# open-bldc-logic.net
KiCad netlist of a schematic drawn in EAGLE
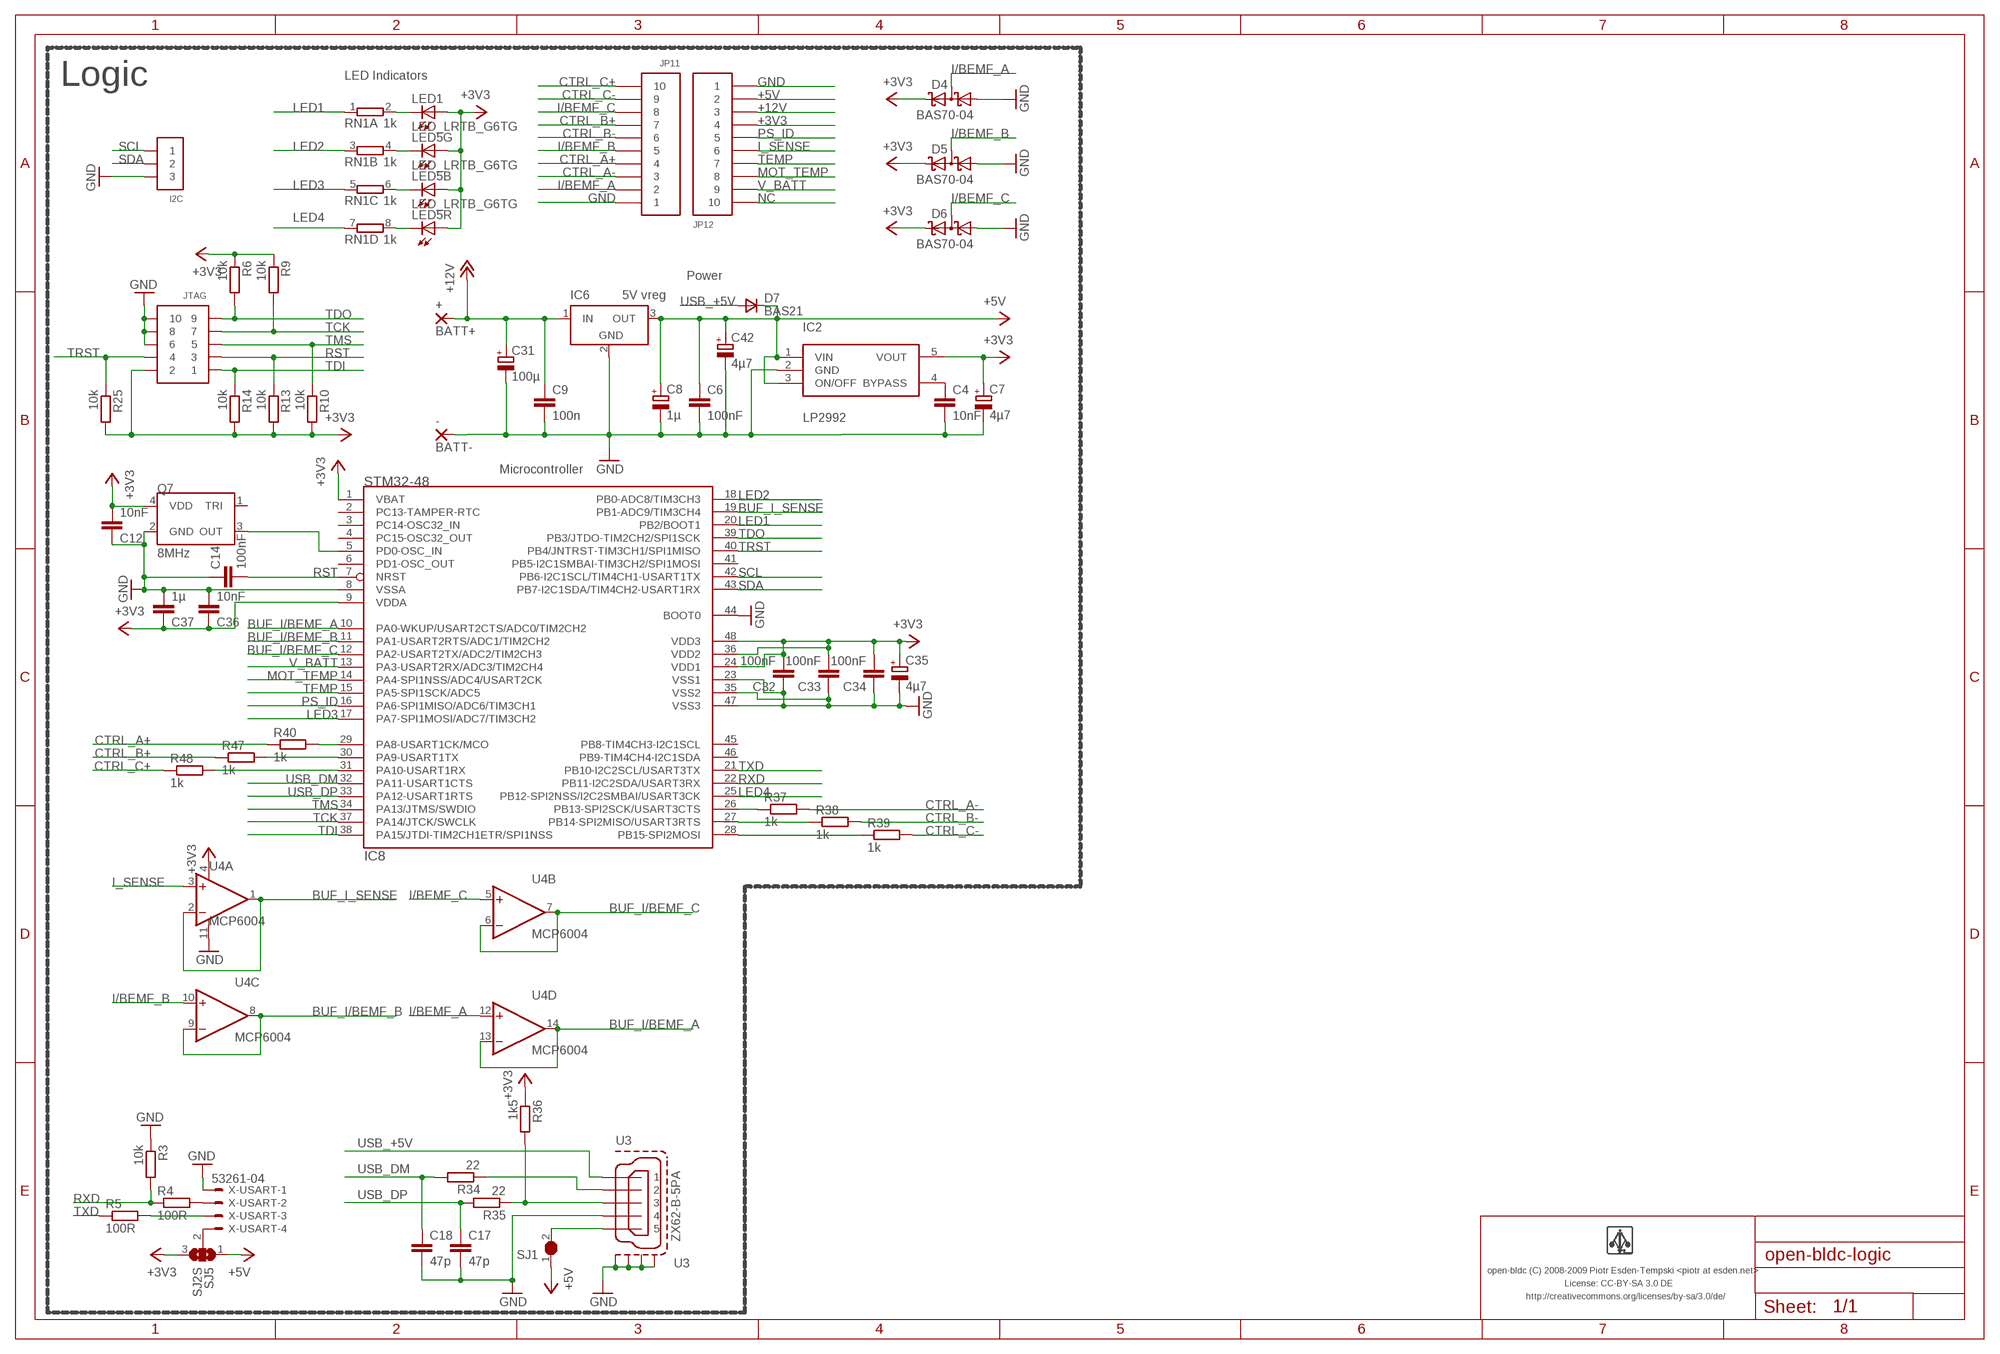
[diagram p0: schematic, sheet 1]

(export (version "E")
  (design (tool "Eeschema 10.0.6"))
  (components
    (comp (ref "+")
      (value "BATT+")
      (footprint "eagle-import:SMD2,54-5,08")
      (libsource (lib "eagle-import") (part "SMD5"))
    )
    (comp (ref "-")
      (value "BATT-")
      (footprint "eagle-import:SMD2,54-5,08")
      (libsource (lib "eagle-import") (part "SMD5"))
    )
    (comp (ref "C4")
      (value "10nF")
      (footprint "eagle-import:C0603")
      (libsource (lib "eagle-import") (part "C-EUC0603"))
    )
    (comp (ref "C6")
      (value "100nF")
      (footprint "eagle-import:C0603")
      (libsource (lib "eagle-import") (part "C-EUC0603"))
    )
    (comp (ref "C7")
      (value "4µ7")
      (footprint "eagle-import:A_3216-18R")
      (libsource (lib "eagle-import") (part "CPOL-EUA/3216-18R"))
    )
    (comp (ref "C8")
      (value "1µ")
      (footprint "eagle-import:A_3216-18R")
      (libsource (lib "eagle-import") (part "CPOL-EUA/3216-18R"))
    )
    (comp (ref "C9")
      (value "100n")
      (footprint "eagle-import:C0603")
      (libsource (lib "eagle-import") (part "C-EUC0603"))
    )
    (comp (ref "C12")
      (value "10nF")
      (footprint "eagle-import:C0603")
      (libsource (lib "eagle-import") (part "C-EUC0603"))
    )
    (comp (ref "C14")
      (value "100nF")
      (footprint "eagle-import:C0603")
      (libsource (lib "eagle-import") (part "C-EUC0603"))
    )
    (comp (ref "C17")
      (value "47p")
      (footprint "eagle-import:C0603")
      (libsource (lib "eagle-import") (part "C-EUC0603"))
    )
    (comp (ref "C18")
      (value "47p")
      (footprint "eagle-import:C0603")
      (libsource (lib "eagle-import") (part "C-EUC0603"))
    )
    (comp (ref "C31")
      (value "100µ")
      (footprint "eagle-import:D_7343-31R")
      (libsource (lib "eagle-import") (part "CPOL-EUD/7343-31R"))
    )
    (comp (ref "C32")
      (value "100nF")
      (footprint "eagle-import:C0603")
      (libsource (lib "eagle-import") (part "C-EUC0603"))
    )
    (comp (ref "C33")
      (value "100nF")
      (footprint "eagle-import:C0603")
      (libsource (lib "eagle-import") (part "C-EUC0603"))
    )
    (comp (ref "C34")
      (value "100nF")
      (footprint "eagle-import:C0603")
      (libsource (lib "eagle-import") (part "C-EUC0603"))
    )
    (comp (ref "C35")
      (value "4µ7")
      (footprint "eagle-import:A_3216-18R")
      (libsource (lib "eagle-import") (part "CPOL-EUA/3216-18R"))
    )
    (comp (ref "C36")
      (value "10nF")
      (footprint "eagle-import:C0603")
      (libsource (lib "eagle-import") (part "C-EUC0603"))
    )
    (comp (ref "C37")
      (value "1µ")
      (footprint "eagle-import:C0603")
      (libsource (lib "eagle-import") (part "C-EUC0603"))
    )
    (comp (ref "C42")
      (value "4µ7")
      (footprint "eagle-import:A_3216-18R")
      (libsource (lib "eagle-import") (part "CPOL-EUA/3216-18R"))
    )
    (comp (ref "D4")
      (value "BAS70-04")
      (footprint "eagle-import:SOT23")
      (libsource (lib "eagle-import") (part "BAS70-04"))
    )
    (comp (ref "D5")
      (value "BAS70-04")
      (footprint "eagle-import:SOT23")
      (libsource (lib "eagle-import") (part "BAS70-04"))
    )
    (comp (ref "D6")
      (value "BAS70-04")
      (footprint "eagle-import:SOT23")
      (libsource (lib "eagle-import") (part "BAS70-04"))
    )
    (comp (ref "D7")
      (value "BAS21")
      (footprint "eagle-import:SOT-23")
      (libsource (lib "eagle-import") (part "VAR2SOT23"))
    )
    (comp (ref "I2C")
      (value "PIN_HDR_EDG_1.27MM_3-1")
      (footprint "eagle-import:PIN_HDR_EDG_1.27MM_3-1")
      (libsource (lib "eagle-import") (part "PIN_HDR_EDG_1.27MM_3-1"))
    )
    (comp (ref "IC2")
      (value "LP2992")
      (footprint "eagle-import:SOT23-5")
      (libsource (lib "eagle-import") (part "LP2992"))
    )
    (comp (ref "IC6")
      (value "5V vreg")
      (footprint "eagle-import:SOT223")
      (libsource (lib "eagle-import") (part "LT1129CST5"))
    )
    (comp (ref "IC8")
      (value "STM32-48")
      (footprint "eagle-import:LQFP48")
      (libsource (lib "eagle-import") (part "STM32-48"))
    )
    (comp (ref "JP11")
      (value "PIN_HDR_1.27MM_10")
      (footprint "eagle-import:PIN_HDR_1.27MM_10")
      (libsource (lib "eagle-import") (part "PIN_HDR_1.27MM_10_TH"))
    )
    (comp (ref "JP12")
      (value "PIN_HDR_1.27MM_10")
      (footprint "eagle-import:PIN_HDR_1.27MM_10")
      (libsource (lib "eagle-import") (part "PIN_HDR_1.27MM_10_TH"))
    )
    (comp (ref "JTAG")
      (value "PIN_HDR_EDG_1.27MM_5-2")
      (footprint "eagle-import:PIN_HDR_EDG_1.27MM_5-2")
      (libsource (lib "eagle-import") (part "PIN_HDR_EDG_1.27MM_5-2"))
    )
    (comp (ref "LED1")
      (value "AMBER")
      (footprint "eagle-import:CHIP-LED0603")
      (libsource (lib "eagle-import") (part "LEDCHIP-LED0603"))
    )
    (comp (ref "LED5")
      (value "LED_LRTB_G6TG")
      (footprint "eagle-import:PLCC6")
      (libsource (lib "eagle-import") (part "LED_LRTB_G6TG"))
    )
    (comp (ref "Q7")
      (value "8MHz")
      (footprint "eagle-import:ASE_OSCILLATOR")
      (libsource (lib "eagle-import") (part "ASE_ASCILLATOR"))
    )
    (comp (ref "R3")
      (value "10k")
      (footprint "eagle-import:R0603")
      (libsource (lib "eagle-import") (part "R-EU_R0603"))
    )
    (comp (ref "R4")
      (value "100R")
      (footprint "eagle-import:R0603")
      (libsource (lib "eagle-import") (part "R-EU_R0603"))
    )
    (comp (ref "R5")
      (value "100R")
      (footprint "eagle-import:R0603")
      (libsource (lib "eagle-import") (part "R-EU_R0603"))
    )
    (comp (ref "R6")
      (value "10k")
      (footprint "eagle-import:R0603")
      (libsource (lib "eagle-import") (part "R-EU_R0603"))
    )
    (comp (ref "R9")
      (value "10k")
      (footprint "eagle-import:R0603")
      (libsource (lib "eagle-import") (part "R-EU_R0603"))
    )
    (comp (ref "R10")
      (value "10k")
      (footprint "eagle-import:R0603")
      (libsource (lib "eagle-import") (part "R-EU_R0603"))
    )
    (comp (ref "R13")
      (value "10k")
      (footprint "eagle-import:R0603")
      (libsource (lib "eagle-import") (part "R-EU_R0603"))
    )
    (comp (ref "R14")
      (value "10k")
      (footprint "eagle-import:R0603")
      (libsource (lib "eagle-import") (part "R-EU_R0603"))
    )
    (comp (ref "R25")
      (value "10k")
      (footprint "eagle-import:R0603")
      (libsource (lib "eagle-import") (part "R-EU_R0603"))
    )
    (comp (ref "R34")
      (value "22")
      (footprint "eagle-import:R0603")
      (libsource (lib "eagle-import") (part "R-EU_R0603"))
    )
    (comp (ref "R35")
      (value "22")
      (footprint "eagle-import:R0603")
      (libsource (lib "eagle-import") (part "R-EU_R0603"))
    )
    (comp (ref "R36")
      (value "1k5")
      (footprint "eagle-import:R0603")
      (libsource (lib "eagle-import") (part "R-EU_R0603"))
    )
    (comp (ref "R37")
      (value "1k")
      (footprint "eagle-import:R0603")
      (libsource (lib "eagle-import") (part "R-EU_R0603"))
    )
    (comp (ref "R38")
      (value "1k")
      (footprint "eagle-import:R0603")
      (libsource (lib "eagle-import") (part "R-EU_R0603"))
    )
    (comp (ref "R39")
      (value "1k")
      (footprint "eagle-import:R0603")
      (libsource (lib "eagle-import") (part "R-EU_R0603"))
    )
    (comp (ref "R40")
      (value "1k")
      (footprint "eagle-import:R0603")
      (libsource (lib "eagle-import") (part "R-EU_R0603"))
    )
    (comp (ref "R47")
      (value "1k")
      (footprint "eagle-import:R0603")
      (libsource (lib "eagle-import") (part "R-EU_R0603"))
    )
    (comp (ref "R48")
      (value "1k")
      (footprint "eagle-import:R0603")
      (libsource (lib "eagle-import") (part "R-EU_R0603"))
    )
    (comp (ref "RN1")
      (value "1k")
      (footprint "eagle-import:R4N1206")
      (libsource (lib "eagle-import") (part "R4N1206"))
    )
    (comp (ref "SJ1")
      (value "SJ1S")
      (footprint "eagle-import:SJ1S")
      (libsource (lib "eagle-import") (part "SJ1S"))
    )
    (comp (ref "SJ5")
      (value "SJ2S")
      (footprint "eagle-import:SJ2S")
      (libsource (lib "eagle-import") (part "SJ2S"))
    )
    (comp (ref "U3")
      (value "ZX62-B-5PA")
      (footprint "eagle-import:ZX62-B-5PA")
      (libsource (lib "eagle-import") (part "ZX62-B-5PA"))
    )
    (comp (ref "U4")
      (value "MCP6004")
      (footprint "eagle-import:TSSOP_14")
      (libsource (lib "eagle-import") (part "MCP6004"))
    )
    (comp (ref "X-USART")
      (value "53261-04")
      (footprint "eagle-import:53261-04")
      (libsource (lib "eagle-import") (part "53?-04261"))
    )
  )
  (nets
    (net (code "1") (name "+3V3") (class "Default")
      (node (ref "C12") (pin "2") (pinfunction "2_2") (pintype "passive"))
      (node (ref "C32") (pin "2") (pinfunction "2_2") (pintype "passive"))
      (node (ref "C33") (pin "2") (pinfunction "2_2") (pintype "passive"))
      (node (ref "C34") (pin "2") (pinfunction "2_2") (pintype "passive"))
      (node (ref "C35") (pin "+") (pinfunction "+_+") (pintype "passive"))
      (node (ref "C36") (pin "1") (pinfunction "1_1") (pintype "passive"))
      (node (ref "C37") (pin "1") (pinfunction "1_1") (pintype "passive"))
      (node (ref "C7") (pin "+") (pinfunction "+_+") (pintype "passive"))
      (node (ref "D4") (pin "2") (pinfunction "C2_2") (pintype "passive"))
      (node (ref "D5") (pin "2") (pinfunction "C2_2") (pintype "passive"))
      (node (ref "D6") (pin "2") (pinfunction "C2_2") (pintype "passive"))
      (node (ref "IC2") (pin "5") (pinfunction "VOUT_5") (pintype "bidirectional"))
      (node (ref "IC8") (pin "1") (pinfunction "VBAT_1") (pintype "power_in"))
      (node (ref "IC8") (pin "24") (pinfunction "VDD1_24") (pintype "power_in"))
      (node (ref "IC8") (pin "36") (pinfunction "VDD2_36") (pintype "power_in"))
      (node (ref "IC8") (pin "48") (pinfunction "VDD3_48") (pintype "power_in"))
      (node (ref "IC8") (pin "9") (pinfunction "VDDA_9") (pintype "power_in"))
      (node (ref "JP12") (pin "P$4") (pinfunction "4_P$4") (pintype "bidirectional"))
      (node (ref "JTAG") (pin "P$2") (pinfunction "2_P$2") (pintype "bidirectional"))
      (node (ref "LED1") (pin "A") (pinfunction "A_A") (pintype "passive"))
      (node (ref "LED5") (pin "A1") (pinfunction "A_A1") (pintype "passive"))
      (node (ref "LED5") (pin "A2") (pinfunction "A_A2") (pintype "passive"))
      (node (ref "LED5") (pin "A3") (pinfunction "A_A3") (pintype "passive"))
      (node (ref "Q7") (pin "4") (pinfunction "VDD_4") (pintype "power_in"))
      (node (ref "R10") (pin "2") (pinfunction "2_2") (pintype "passive"))
      (node (ref "R13") (pin "2") (pinfunction "2_2") (pintype "passive"))
      (node (ref "R14") (pin "2") (pinfunction "2_2") (pintype "passive"))
      (node (ref "R25") (pin "2") (pinfunction "2_2") (pintype "passive"))
      (node (ref "R36") (pin "1") (pinfunction "1_1") (pintype "passive"))
      (node (ref "R6") (pin "1") (pinfunction "1_1") (pintype "passive"))
      (node (ref "R9") (pin "1") (pinfunction "1_1") (pintype "passive"))
      (node (ref "SJ5") (pin "3") (pinfunction "3_3") (pintype "passive"))
      (node (ref "U4") (pin "4") (pinfunction "V+_4") (pintype "power_in"))
    )
    (net (code "2") (name "+5V") (class "Default")
      (node (ref "C42") (pin "+") (pinfunction "+_+") (pintype "passive"))
      (node (ref "C6") (pin "1") (pinfunction "1_1") (pintype "passive"))
      (node (ref "C8") (pin "+") (pinfunction "+_+") (pintype "passive"))
      (node (ref "D7") (pin "1") (pinfunction "C_1") (pintype "passive"))
      (node (ref "IC2") (pin "1") (pinfunction "VIN_1") (pintype "bidirectional"))
      (node (ref "IC2") (pin "3") (pinfunction "ON/OFF_3") (pintype "bidirectional"))
      (node (ref "IC6") (pin "3") (pinfunction "OUT_3") (pintype "power_in"))
      (node (ref "JP12") (pin "P$2") (pinfunction "2_P$2") (pintype "bidirectional"))
      (node (ref "SJ1") (pin "1") (pinfunction "1_1") (pintype "passive"))
      (node (ref "SJ5") (pin "1") (pinfunction "1_1") (pintype "passive"))
    )
    (net (code "3") (name "+12V") (class "Default")
      (node (ref "+") (pin "1") (pinfunction "P_1") (pintype "passive"))
      (node (ref "C31") (pin "+") (pinfunction "+_+") (pintype "passive"))
      (node (ref "C9") (pin "1") (pinfunction "1_1") (pintype "passive"))
      (node (ref "IC6") (pin "1") (pinfunction "IN_1") (pintype "input"))
      (node (ref "JP12") (pin "P$3") (pinfunction "3_P$3") (pintype "bidirectional"))
    )
    (net (code "4") (name "/BUF_I_SENSE") (class "Default")
      (node (ref "IC8") (pin "19") (pinfunction "PB1-ADC9/TIM3CH4_19") (pintype "bidirectional"))
      (node (ref "U4") (pin "1") (pinfunction "OUT_1") (pintype "output"))
      (node (ref "U4") (pin "2") (pinfunction "-IN_2") (pintype "input"))
    )
    (net (code "5") (name "/BUF_I{slash}BEMF_A") (class "Default")
      (node (ref "IC8") (pin "10") (pinfunction "PA0-WKUP/USART2CTS/ADC0/TIM2CH2_10") (pintype "bidirectional"))
      (node (ref "U4") (pin "13") (pinfunction "-IN_13") (pintype "input"))
      (node (ref "U4") (pin "14") (pinfunction "OUT_14") (pintype "output"))
    )
    (net (code "6") (name "/BUF_I{slash}BEMF_B") (class "Default")
      (node (ref "IC8") (pin "11") (pinfunction "PA1-USART2RTS/ADC1/TIM2CH2_11") (pintype "bidirectional"))
      (node (ref "U4") (pin "8") (pinfunction "OUT_8") (pintype "output"))
      (node (ref "U4") (pin "9") (pinfunction "-IN_9") (pintype "input"))
    )
    (net (code "7") (name "/BUF_I{slash}BEMF_C") (class "Default")
      (node (ref "IC8") (pin "12") (pinfunction "PA2-USART2TX/ADC2/TIM2CH3_12") (pintype "bidirectional"))
      (node (ref "U4") (pin "6") (pinfunction "-IN_6") (pintype "input"))
      (node (ref "U4") (pin "7") (pinfunction "OUT_7") (pintype "output"))
    )
    (net (code "8") (name "/CTRL_A+") (class "Default")
      (node (ref "JP11") (pin "P$4") (pinfunction "4_P$4") (pintype "bidirectional"))
      (node (ref "R40") (pin "1") (pinfunction "1_1") (pintype "passive"))
    )
    (net (code "9") (name "/CTRL_A-") (class "Default")
      (node (ref "JP11") (pin "P$3") (pinfunction "3_P$3") (pintype "bidirectional"))
      (node (ref "R37") (pin "2") (pinfunction "2_2") (pintype "passive"))
    )
    (net (code "10") (name "/CTRL_B+") (class "Default")
      (node (ref "JP11") (pin "P$7") (pinfunction "7_P$7") (pintype "bidirectional"))
      (node (ref "R47") (pin "1") (pinfunction "1_1") (pintype "passive"))
    )
    (net (code "11") (name "/CTRL_B-") (class "Default")
      (node (ref "JP11") (pin "P$6") (pinfunction "6_P$6") (pintype "bidirectional"))
      (node (ref "R38") (pin "2") (pinfunction "2_2") (pintype "passive"))
    )
    (net (code "12") (name "/CTRL_C+") (class "Default")
      (node (ref "JP11") (pin "P$10") (pinfunction "10_P$10") (pintype "bidirectional"))
      (node (ref "R48") (pin "1") (pinfunction "1_1") (pintype "passive"))
    )
    (net (code "13") (name "/CTRL_C-") (class "Default")
      (node (ref "JP11") (pin "P$9") (pinfunction "9_P$9") (pintype "bidirectional"))
      (node (ref "R39") (pin "2") (pinfunction "2_2") (pintype "passive"))
    )
    (net (code "14") (name "/I_SENSE") (class "Default")
      (node (ref "JP12") (pin "P$6") (pinfunction "6_P$6") (pintype "bidirectional"))
      (node (ref "U4") (pin "3") (pinfunction "+IN_3") (pintype "input"))
    )
    (net (code "15") (name "/I{slash}BEMF_A") (class "Default")
      (node (ref "D4") (pin "3") (pinfunction "C1A2_3") (pintype "passive"))
      (node (ref "JP11") (pin "P$2") (pinfunction "2_P$2") (pintype "bidirectional"))
      (node (ref "U4") (pin "12") (pinfunction "+IN_12") (pintype "input"))
    )
    (net (code "16") (name "/I{slash}BEMF_B") (class "Default")
      (node (ref "D5") (pin "3") (pinfunction "C1A2_3") (pintype "passive"))
      (node (ref "JP11") (pin "P$5") (pinfunction "5_P$5") (pintype "bidirectional"))
      (node (ref "U4") (pin "10") (pinfunction "+IN_10") (pintype "input"))
    )
    (net (code "17") (name "/I{slash}BEMF_C") (class "Default")
      (node (ref "D6") (pin "3") (pinfunction "C1A2_3") (pintype "passive"))
      (node (ref "JP11") (pin "P$8") (pinfunction "8_P$8") (pintype "bidirectional"))
      (node (ref "U4") (pin "5") (pinfunction "+IN_5") (pintype "input"))
    )
    (net (code "18") (name "/LED1") (class "Default")
      (node (ref "IC8") (pin "20") (pinfunction "PB2/BOOT1_20") (pintype "bidirectional"))
      (node (ref "RN1") (pin "1") (pinfunction "1_1") (pintype "passive"))
    )
    (net (code "19") (name "/LED2") (class "Default")
      (node (ref "IC8") (pin "18") (pinfunction "PB0-ADC8/TIM3CH3_18") (pintype "bidirectional"))
      (node (ref "RN1") (pin "3") (pinfunction "1_3") (pintype "passive"))
    )
    (net (code "20") (name "/LED3") (class "Default")
      (node (ref "IC8") (pin "17") (pinfunction "PA7-SPI1MOSI/ADC7/TIM3CH2_17") (pintype "bidirectional"))
      (node (ref "RN1") (pin "5") (pinfunction "1_5") (pintype "passive"))
    )
    (net (code "21") (name "/LED4") (class "Default")
      (node (ref "IC8") (pin "25") (pinfunction "PB12-SPI2NSS/I2C2SMBAI/USART3CK_25") (pintype "bidirectional"))
      (node (ref "RN1") (pin "7") (pinfunction "1_7") (pintype "passive"))
    )
    (net (code "22") (name "/MOT_TEMP") (class "Default")
      (node (ref "IC8") (pin "14") (pinfunction "PA4-SPI1NSS/ADC4/USART2CK_14") (pintype "bidirectional"))
      (node (ref "JP12") (pin "P$8") (pinfunction "8_P$8") (pintype "bidirectional"))
    )
    (net (code "23") (name "/NC") (class "Default")
      (node (ref "JP12") (pin "P$10") (pinfunction "10_P$10") (pintype "bidirectional"))
    )
    (net (code "24") (name "/PS_ID") (class "Default")
      (node (ref "IC8") (pin "16") (pinfunction "PA6-SPI1MISO/ADC6/TIM3CH1_16") (pintype "bidirectional"))
      (node (ref "JP12") (pin "P$5") (pinfunction "5_P$5") (pintype "bidirectional"))
    )
    (net (code "25") (name "/RST") (class "Default")
      (node (ref "C14") (pin "2") (pinfunction "2_2") (pintype "passive"))
      (node (ref "IC8") (pin "7") (pinfunction "NRST_7") (pintype "bidirectional"))
      (node (ref "JTAG") (pin "P$3") (pinfunction "3_P$3") (pintype "bidirectional"))
      (node (ref "R13") (pin "1") (pinfunction "1_1") (pintype "passive"))
    )
    (net (code "26") (name "/RXD") (class "Default")
      (node (ref "IC8") (pin "22") (pinfunction "PB11-I2C2SDA/USART3RX_22") (pintype "bidirectional"))
      (node (ref "R3") (pin "2") (pinfunction "2_2") (pintype "passive"))
      (node (ref "R4") (pin "1") (pinfunction "1_1") (pintype "passive"))
    )
    (net (code "27") (name "/SCL") (class "Default")
      (node (ref "I2C") (pin "P$1") (pinfunction "1_P$1") (pintype "bidirectional"))
      (node (ref "IC8") (pin "42") (pinfunction "PB6-I2C1SCL/TIM4CH1-USART1TX_42") (pintype "bidirectional"))
    )
    (net (code "28") (name "/SDA") (class "Default")
      (node (ref "I2C") (pin "P$2") (pinfunction "2_P$2") (pintype "bidirectional"))
      (node (ref "IC8") (pin "43") (pinfunction "PB7-I2C1SDA/TIM4CH2-USART1RX_43") (pintype "bidirectional"))
    )
    (net (code "29") (name "/TCK") (class "Default")
      (node (ref "IC8") (pin "37") (pinfunction "PA14/JTCK/SWCLK_37") (pintype "bidirectional"))
      (node (ref "JTAG") (pin "P$7") (pinfunction "7_P$7") (pintype "bidirectional"))
      (node (ref "R9") (pin "2") (pinfunction "2_2") (pintype "passive"))
    )
    (net (code "30") (name "/TDI") (class "Default")
      (node (ref "IC8") (pin "38") (pinfunction "PA15/JTDI-TIM2CH1ETR/SPI1NSS_38") (pintype "bidirectional"))
      (node (ref "JTAG") (pin "P$1") (pinfunction "1_P$1") (pintype "bidirectional"))
      (node (ref "R14") (pin "1") (pinfunction "1_1") (pintype "passive"))
    )
    (net (code "31") (name "/TDO") (class "Default")
      (node (ref "IC8") (pin "39") (pinfunction "PB3/JTDO-TIM2CH2/SPI1SCK_39") (pintype "bidirectional"))
      (node (ref "JTAG") (pin "P$9") (pinfunction "9_P$9") (pintype "bidirectional"))
      (node (ref "R6") (pin "2") (pinfunction "2_2") (pintype "passive"))
    )
    (net (code "32") (name "/TEMP") (class "Default")
      (node (ref "IC8") (pin "15") (pinfunction "PA5-SPI1SCK/ADC5_15") (pintype "bidirectional"))
      (node (ref "JP12") (pin "P$7") (pinfunction "7_P$7") (pintype "bidirectional"))
    )
    (net (code "33") (name "/TMS") (class "Default")
      (node (ref "IC8") (pin "34") (pinfunction "PA13/JTMS/SWDIO_34") (pintype "bidirectional"))
      (node (ref "JTAG") (pin "P$5") (pinfunction "5_P$5") (pintype "bidirectional"))
      (node (ref "R10") (pin "1") (pinfunction "1_1") (pintype "passive"))
    )
    (net (code "34") (name "/TRST") (class "Default")
      (node (ref "IC8") (pin "40") (pinfunction "PB4/JNTRST-TIM3CH1/SPI1MISO_40") (pintype "bidirectional"))
      (node (ref "JTAG") (pin "P$4") (pinfunction "4_P$4") (pintype "bidirectional"))
      (node (ref "R25") (pin "1") (pinfunction "1_1") (pintype "passive"))
    )
    (net (code "35") (name "/TXD") (class "Default")
      (node (ref "IC8") (pin "21") (pinfunction "PB10-I2C2SCL/USART3TX_21") (pintype "bidirectional"))
      (node (ref "R5") (pin "1") (pinfunction "1_1") (pintype "passive"))
    )
    (net (code "36") (name "/USB_+5V") (class "Default")
      (node (ref "D7") (pin "3") (pinfunction "A_3") (pintype "passive"))
      (node (ref "U3") (pin "PIN_1") (pinfunction "1_PIN_1") (pintype "input"))
    )
    (net (code "37") (name "/USB_DM") (class "Default")
      (node (ref "C18") (pin "1") (pinfunction "1_1") (pintype "passive"))
      (node (ref "IC8") (pin "32") (pinfunction "PA11-USART1CTS_32") (pintype "bidirectional"))
      (node (ref "R34") (pin "2") (pinfunction "2_2") (pintype "passive"))
    )
    (net (code "38") (name "/USB_DP") (class "Default")
      (node (ref "C17") (pin "1") (pinfunction "1_1") (pintype "passive"))
      (node (ref "IC8") (pin "33") (pinfunction "PA12-USART1RTS_33") (pintype "bidirectional"))
      (node (ref "R35") (pin "2") (pinfunction "2_2") (pintype "passive"))
    )
    (net (code "39") (name "/V_BATT") (class "Default")
      (node (ref "IC8") (pin "13") (pinfunction "PA3-USART2RX/ADC3/TIM2CH4_13") (pintype "bidirectional"))
      (node (ref "JP12") (pin "P$9") (pinfunction "9_P$9") (pintype "bidirectional"))
    )
    (net (code "40") (name "GND") (class "Default")
      (node (ref "-") (pin "1") (pinfunction "P_1") (pintype "passive"))
      (node (ref "C12") (pin "1") (pinfunction "1_1") (pintype "passive"))
      (node (ref "C14") (pin "1") (pinfunction "1_1") (pintype "passive"))
      (node (ref "C17") (pin "2") (pinfunction "2_2") (pintype "passive"))
      (node (ref "C18") (pin "2") (pinfunction "2_2") (pintype "passive"))
      (node (ref "C31") (pin "-") (pinfunction "-_-") (pintype "passive"))
      (node (ref "C32") (pin "1") (pinfunction "1_1") (pintype "passive"))
      (node (ref "C33") (pin "1") (pinfunction "1_1") (pintype "passive"))
      (node (ref "C34") (pin "1") (pinfunction "1_1") (pintype "passive"))
      (node (ref "C35") (pin "-") (pinfunction "-_-") (pintype "passive"))
      (node (ref "C36") (pin "2") (pinfunction "2_2") (pintype "passive"))
      (node (ref "C37") (pin "2") (pinfunction "2_2") (pintype "passive"))
      (node (ref "C4") (pin "2") (pinfunction "2_2") (pintype "passive"))
      (node (ref "C42") (pin "-") (pinfunction "-_-") (pintype "passive"))
      (node (ref "C6") (pin "2") (pinfunction "2_2") (pintype "passive"))
      (node (ref "C7") (pin "-") (pinfunction "-_-") (pintype "passive"))
      (node (ref "C8") (pin "-") (pinfunction "-_-") (pintype "passive"))
      (node (ref "C9") (pin "2") (pinfunction "2_2") (pintype "passive"))
      (node (ref "D4") (pin "1") (pinfunction "A1_1") (pintype "passive"))
      (node (ref "D5") (pin "1") (pinfunction "A1_1") (pintype "passive"))
      (node (ref "D6") (pin "1") (pinfunction "A1_1") (pintype "passive"))
      (node (ref "I2C") (pin "P$3") (pinfunction "3_P$3") (pintype "bidirectional"))
      (node (ref "IC2") (pin "2") (pinfunction "GND_2") (pintype "bidirectional"))
      (node (ref "IC6") (pin "2") (pinfunction "GND_2") (pintype "power_in"))
      (node (ref "IC8") (pin "23") (pinfunction "VSS1_23") (pintype "power_in"))
      (node (ref "IC8") (pin "35") (pinfunction "VSS2_35") (pintype "power_in"))
      (node (ref "IC8") (pin "44") (pinfunction "BOOT0_44") (pintype "input"))
      (node (ref "IC8") (pin "47") (pinfunction "VSS3_47") (pintype "power_in"))
      (node (ref "IC8") (pin "8") (pinfunction "VSSA_8") (pintype "power_in"))
      (node (ref "JP11") (pin "P$1") (pinfunction "1_P$1") (pintype "bidirectional"))
      (node (ref "JP12") (pin "P$1") (pinfunction "1_P$1") (pintype "bidirectional"))
      (node (ref "JTAG") (pin "P$10") (pinfunction "10_P$10") (pintype "bidirectional"))
      (node (ref "JTAG") (pin "P$6") (pinfunction "6_P$6") (pintype "bidirectional"))
      (node (ref "JTAG") (pin "P$8") (pinfunction "8_P$8") (pintype "bidirectional"))
      (node (ref "Q7") (pin "2") (pinfunction "GND_2") (pintype "power_in"))
      (node (ref "R3") (pin "1") (pinfunction "1_1") (pintype "passive"))
      (node (ref "U3") (pin "GND_LEFT") (pinfunction "S1_GND_LEFT") (pintype "passive"))
      (node (ref "U3") (pin "GND_RIGHT") (pinfunction "S2_GND_RIGHT") (pintype "passive"))
      (node (ref "U3") (pin "GND_UP_LEFT") (pinfunction "S3_GND_UP_LEFT") (pintype "passive"))
      (node (ref "U3") (pin "GND_UP_RIGHT") (pinfunction "S4_GND_UP_RIGHT") (pintype "passive"))
      (node (ref "U3") (pin "PIN_4") (pinfunction "4_PIN_4") (pintype "input"))
      (node (ref "U4") (pin "11") (pinfunction "V-_11") (pintype "power_in"))
      (node (ref "X-USART") (pin "1") (pinfunction "S_1") (pintype "passive"))
    )
    (net (code "41") (name "Net-(IC2-BYPASS)") (class "Default")
      (node (ref "C4") (pin "1") (pinfunction "1_1") (pintype "passive"))
      (node (ref "IC2") (pin "4") (pinfunction "BYPASS_4") (pintype "bidirectional"))
    )
    (net (code "42") (name "Net-(IC8-PA8-USART1CK{slash}MCO)") (class "Default")
      (node (ref "IC8") (pin "29") (pinfunction "PA8-USART1CK/MCO_29") (pintype "bidirectional"))
      (node (ref "R40") (pin "2") (pinfunction "2_2") (pintype "passive"))
    )
    (net (code "43") (name "Net-(IC8-PA9-USART1TX)") (class "Default")
      (node (ref "IC8") (pin "30") (pinfunction "PA9-USART1TX_30") (pintype "bidirectional"))
      (node (ref "R47") (pin "2") (pinfunction "2_2") (pintype "passive"))
    )
    (net (code "44") (name "Net-(IC8-PA10-USART1RX)") (class "Default")
      (node (ref "IC8") (pin "31") (pinfunction "PA10-USART1RX_31") (pintype "bidirectional"))
      (node (ref "R48") (pin "2") (pinfunction "2_2") (pintype "passive"))
    )
    (net (code "45") (name "Net-(IC8-PB13-SPI2SCK{slash}USART3CTS)") (class "Default")
      (node (ref "IC8") (pin "26") (pinfunction "PB13-SPI2SCK/USART3CTS_26") (pintype "bidirectional"))
      (node (ref "R37") (pin "1") (pinfunction "1_1") (pintype "passive"))
    )
    (net (code "46") (name "Net-(IC8-PB14-SPI2MISO{slash}USART3RTS)") (class "Default")
      (node (ref "IC8") (pin "27") (pinfunction "PB14-SPI2MISO/USART3RTS_27") (pintype "bidirectional"))
      (node (ref "R38") (pin "1") (pinfunction "1_1") (pintype "passive"))
    )
    (net (code "47") (name "Net-(IC8-PB15-SPI2MOSI)") (class "Default")
      (node (ref "IC8") (pin "28") (pinfunction "PB15-SPI2MOSI_28") (pintype "bidirectional"))
      (node (ref "R39") (pin "1") (pinfunction "1_1") (pintype "passive"))
    )
    (net (code "48") (name "Net-(IC8-PD0-OSC_IN)") (class "Default")
      (node (ref "IC8") (pin "5") (pinfunction "PD0-OSC_IN_5") (pintype "input"))
      (node (ref "Q7") (pin "3") (pinfunction "OUT_3") (pintype "output"))
    )
    (net (code "49") (name "Net-(LED1-PadC)") (class "Default")
      (node (ref "LED1") (pin "C") (pinfunction "C_C") (pintype "passive"))
      (node (ref "RN1") (pin "2") (pinfunction "2_2") (pintype "passive"))
    )
    (net (code "50") (name "Net-(LED5A-C)") (class "Default")
      (node (ref "LED5") (pin "C3") (pinfunction "C_C3") (pintype "passive"))
      (node (ref "RN1") (pin "6") (pinfunction "2_6") (pintype "passive"))
    )
    (net (code "51") (name "Net-(LED5B-C)") (class "Default")
      (node (ref "LED5") (pin "C2") (pinfunction "C_C2") (pintype "passive"))
      (node (ref "RN1") (pin "4") (pinfunction "2_4") (pintype "passive"))
    )
    (net (code "52") (name "Net-(LED5C-C)") (class "Default")
      (node (ref "LED5") (pin "C1") (pinfunction "C_C1") (pintype "passive"))
      (node (ref "RN1") (pin "8") (pinfunction "2_8") (pintype "passive"))
    )
    (net (code "53") (name "Net-(U3-2)") (class "Default")
      (node (ref "R34") (pin "1") (pinfunction "1_1") (pintype "passive"))
      (node (ref "U3") (pin "PIN_2") (pinfunction "2_PIN_2") (pintype "input"))
    )
    (net (code "54") (name "Net-(U3-3)") (class "Default")
      (node (ref "R35") (pin "1") (pinfunction "1_1") (pintype "passive"))
      (node (ref "R36") (pin "2") (pinfunction "2_2") (pintype "passive"))
      (node (ref "U3") (pin "PIN_3") (pinfunction "3_PIN_3") (pintype "input"))
    )
    (net (code "55") (name "Net-(U3-5)") (class "Default")
      (node (ref "SJ1") (pin "2") (pinfunction "2_2") (pintype "passive"))
      (node (ref "U3") (pin "PIN_5") (pinfunction "5_PIN_5") (pintype "input"))
    )
    (net (code "56") (name "Net-(X-USARTB-S)") (class "Default")
      (node (ref "R4") (pin "2") (pinfunction "2_2") (pintype "passive"))
      (node (ref "X-USART") (pin "2") (pinfunction "S_2") (pintype "passive"))
    )
    (net (code "57") (name "Net-(X-USARTC-S)") (class "Default")
      (node (ref "R5") (pin "2") (pinfunction "2_2") (pintype "passive"))
      (node (ref "X-USART") (pin "3") (pinfunction "S_3") (pintype "passive"))
    )
    (net (code "58") (name "Net-(X-USARTD-S)") (class "Default")
      (node (ref "SJ5") (pin "2") (pinfunction "2_2") (pintype "passive"))
      (node (ref "X-USART") (pin "4") (pinfunction "S_4") (pintype "passive"))
    )
    (net (code "59") (name "unconnected-(IC8-PB5-I2C1SMBAI-TIM3CH2{slash}SPI1MOSI-Pad41)") (class "Default")
      (node (ref "IC8") (pin "41") (pinfunction "PB5-I2C1SMBAI-TIM3CH2/SPI1MOSI_41") (pintype "bidirectional"))
    )
    (net (code "60") (name "unconnected-(IC8-PB8-TIM4CH3-I2C1SCL-Pad45)") (class "Default")
      (node (ref "IC8") (pin "45") (pinfunction "PB8-TIM4CH3-I2C1SCL_45") (pintype "bidirectional"))
    )
    (net (code "61") (name "unconnected-(IC8-PB9-TIM4CH4-I2C1SDA-Pad46)") (class "Default")
      (node (ref "IC8") (pin "46") (pinfunction "PB9-TIM4CH4-I2C1SDA_46") (pintype "bidirectional"))
    )
    (net (code "62") (name "unconnected-(IC8-PC13-TAMPER-RTC-Pad2)") (class "Default")
      (node (ref "IC8") (pin "2") (pinfunction "PC13-TAMPER-RTC_2") (pintype "bidirectional"))
    )
    (net (code "63") (name "unconnected-(IC8-PC14-OSC32_IN-Pad3)") (class "Default")
      (node (ref "IC8") (pin "3") (pinfunction "PC14-OSC32_IN_3") (pintype "bidirectional"))
    )
    (net (code "64") (name "unconnected-(IC8-PC15-OSC32_OUT-Pad4)") (class "Default")
      (node (ref "IC8") (pin "4") (pinfunction "PC15-OSC32_OUT_4") (pintype "bidirectional"))
    )
    (net (code "65") (name "unconnected-(IC8-PD1-OSC_OUT-Pad6)") (class "Default")
      (node (ref "IC8") (pin "6") (pinfunction "PD1-OSC_OUT_6") (pintype "output"))
    )
    (net (code "66") (name "unconnected-(Q7-TRI-Pad1)") (class "Default")
      (node (ref "Q7") (pin "1") (pinfunction "TRI_1") (pintype "output"))
    )
  )
)
